# sensor_module_base_16F1454.net
KiCad netlist of a schematic drawn in EAGLE
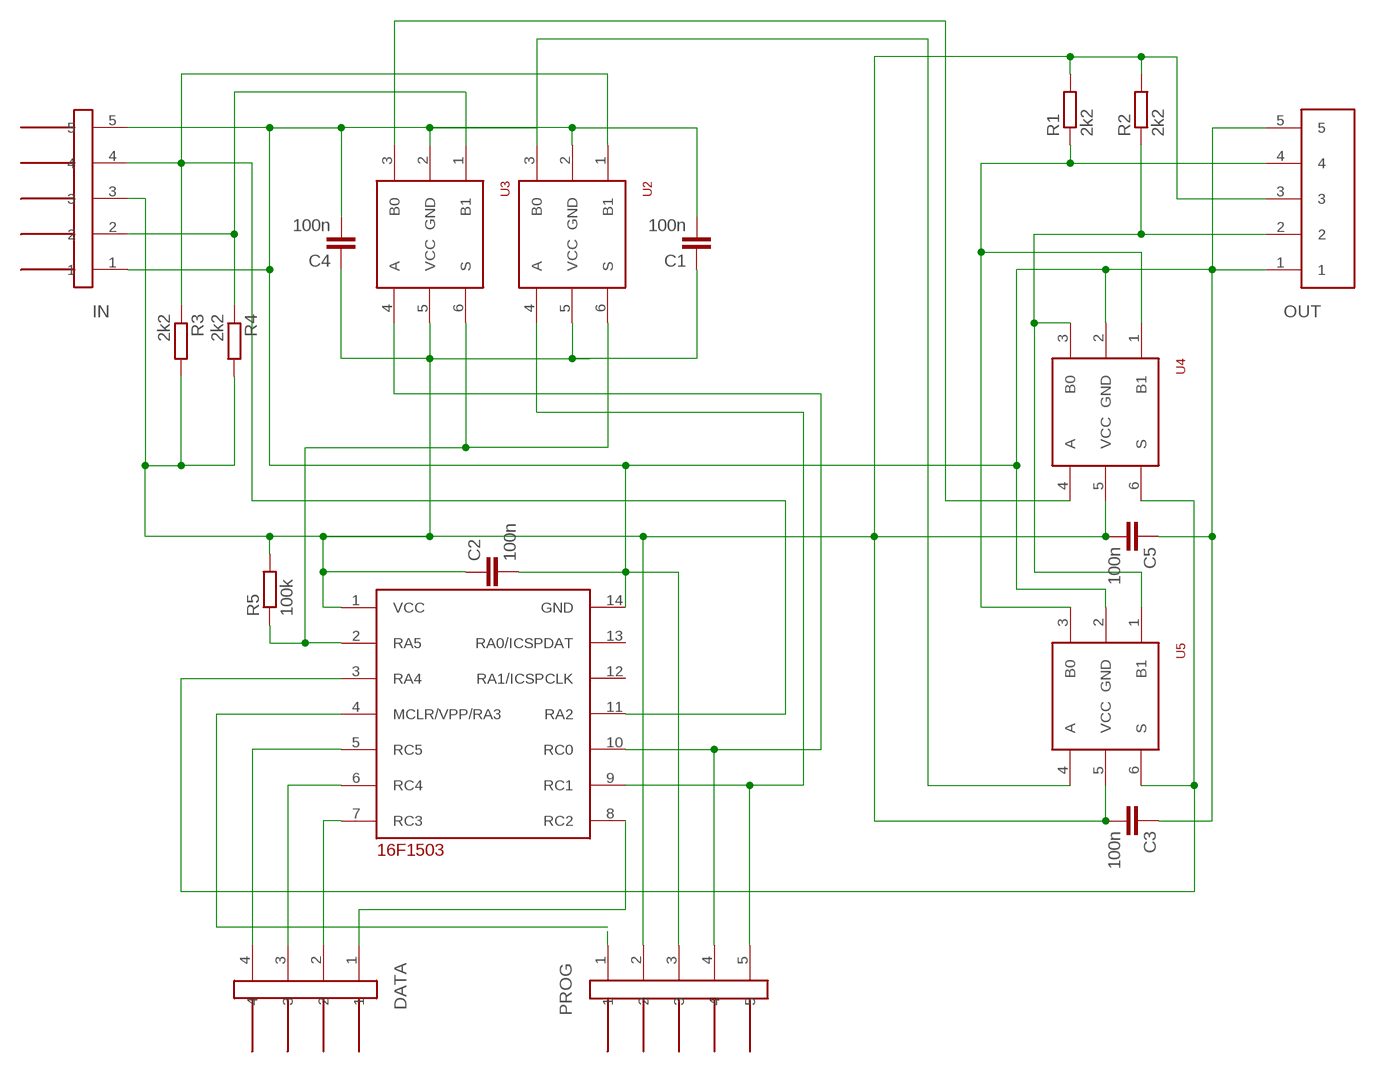
[diagram p0: schematic, sheet 1]

(export (version "E")
  (design (tool "Eeschema 10.0.6"))
  (components
    (comp (ref "C1")
      (value "100n")
      (footprint "eagle-import:C0603K")
      (libsource (lib "eagle-import") (part "C-EUC0603K"))
    )
    (comp (ref "C2")
      (value "100n")
      (footprint "eagle-import:C0603K")
      (libsource (lib "eagle-import") (part "C-EUC0603K"))
    )
    (comp (ref "C3")
      (value "100n")
      (footprint "eagle-import:C0603K")
      (libsource (lib "eagle-import") (part "C-EUC0603K"))
    )
    (comp (ref "C4")
      (value "100n")
      (footprint "eagle-import:C0603K")
      (libsource (lib "eagle-import") (part "C-EUC0603K"))
    )
    (comp (ref "C5")
      (value "100n")
      (footprint "eagle-import:C0603K")
      (libsource (lib "eagle-import") (part "C-EUC0603K"))
    )
    (comp (ref "DATA")
      (value "JUMPER4M")
      (footprint "eagle-import:JUMPER4M")
      (libsource (lib "eagle-import") (part "JUMPER4M"))
    )
    (comp (ref "IN")
      (value "JUMPER5M-90")
      (footprint "eagle-import:JUMPER5M-90")
      (libsource (lib "eagle-import") (part "JUMPER5M-90"))
    )
    (comp (ref "OUT")
      (value "JUMPER5F-90")
      (footprint "eagle-import:JUMPER5F-90")
      (libsource (lib "eagle-import") (part "JUMPER5F-90"))
    )
    (comp (ref "PROG")
      (value "JUMPER5M")
      (footprint "eagle-import:JUMPER5M")
      (libsource (lib "eagle-import") (part "JUMPER5M"))
    )
    (comp (ref "R1")
      (value "2k2")
      (footprint "eagle-import:R0603")
      (libsource (lib "eagle-import") (part "R-EU_R0603"))
    )
    (comp (ref "R2")
      (value "2k2")
      (footprint "eagle-import:R0603")
      (libsource (lib "eagle-import") (part "R-EU_R0603"))
    )
    (comp (ref "R3")
      (value "2k2")
      (footprint "eagle-import:R0603")
      (libsource (lib "eagle-import") (part "R-EU_R0603"))
    )
    (comp (ref "R4")
      (value "2k2")
      (footprint "eagle-import:R0603")
      (libsource (lib "eagle-import") (part "R-EU_R0603"))
    )
    (comp (ref "R5")
      (value "100k")
      (footprint "eagle-import:R0603")
      (libsource (lib "eagle-import") (part "R-EU_R0603"))
    )
    (comp (ref "U1")
      (value "16F1454")
      (footprint "eagle-import:TSSOP14")
      (libsource (lib "eagle-import") (part "16F103-TSSOP"))
    )
    (comp (ref "U2")
      (value "NC7SB3157P6X")
      (footprint "eagle-import:SC70-6L")
      (libsource (lib "eagle-import") (part "NC7SB3157P6X"))
    )
    (comp (ref "U3")
      (value "NC7SB3157P6X")
      (footprint "eagle-import:SC70-6L")
      (libsource (lib "eagle-import") (part "NC7SB3157P6X"))
    )
    (comp (ref "U4")
      (value "NC7SB3157P6X")
      (footprint "eagle-import:SC70-6L")
      (libsource (lib "eagle-import") (part "NC7SB3157P6X"))
    )
    (comp (ref "U5")
      (value "NC7SB3157P6X")
      (footprint "eagle-import:SC70-6L")
      (libsource (lib "eagle-import") (part "NC7SB3157P6X"))
    )
  )
  (nets
    (net (code "1") (name "Net-(U1-GND)") (class "Default")
      (node (ref "C1") (pin "2") (pinfunction "2_2") (pintype "passive"))
      (node (ref "C2") (pin "2") (pinfunction "2_2") (pintype "passive"))
      (node (ref "C3") (pin "1") (pinfunction "1_1") (pintype "passive"))
      (node (ref "C4") (pin "2") (pinfunction "2_2") (pintype "passive"))
      (node (ref "C5") (pin "1") (pinfunction "1_1") (pintype "passive"))
      (node (ref "IN") (pin "1") (pinfunction "1_1") (pintype "bidirectional"))
      (node (ref "IN") (pin "5") (pinfunction "5_5") (pintype "bidirectional"))
      (node (ref "OUT") (pin "1") (pinfunction "1_1") (pintype "bidirectional"))
      (node (ref "OUT") (pin "5") (pinfunction "5_5") (pintype "bidirectional"))
      (node (ref "PROG") (pin "3") (pinfunction "3_3") (pintype "bidirectional"))
      (node (ref "U1") (pin "14") (pinfunction "GND_14") (pintype "power_in"))
      (node (ref "U2") (pin "2") (pinfunction "GND_2") (pintype "power_in"))
      (node (ref "U3") (pin "2") (pinfunction "GND_2") (pintype "power_in"))
      (node (ref "U4") (pin "2") (pinfunction "GND_2") (pintype "power_in"))
      (node (ref "U5") (pin "2") (pinfunction "GND_2") (pintype "power_in"))
    )
    (net (code "2") (name "Net-(U1-MCLR{slash}VPP{slash}RA3)") (class "Default")
      (node (ref "PROG") (pin "1") (pinfunction "1_1") (pintype "bidirectional"))
      (node (ref "U1") (pin "4") (pinfunction "MCLR/VPP/RA3_4") (pintype "bidirectional"))
    )
    (net (code "3") (name "Net-(U1-RA2)") (class "Default")
      (node (ref "IN") (pin "4") (pinfunction "4_4") (pintype "bidirectional"))
      (node (ref "R3") (pin "1") (pinfunction "1_1") (pintype "passive"))
      (node (ref "U1") (pin "11") (pinfunction "RA2_11") (pintype "bidirectional"))
      (node (ref "U2") (pin "1") (pinfunction "B1_1") (pintype "bidirectional"))
    )
    (net (code "4") (name "Net-(U1-RA4)") (class "Default")
      (node (ref "U1") (pin "3") (pinfunction "RA4_3") (pintype "bidirectional"))
      (node (ref "U4") (pin "6") (pinfunction "S_6") (pintype "bidirectional"))
      (node (ref "U5") (pin "6") (pinfunction "S_6") (pintype "bidirectional"))
    )
    (net (code "5") (name "Net-(U1-RA5)") (class "Default")
      (node (ref "R5") (pin "1") (pinfunction "1_1") (pintype "passive"))
      (node (ref "U1") (pin "2") (pinfunction "RA5_2") (pintype "bidirectional"))
      (node (ref "U2") (pin "6") (pinfunction "S_6") (pintype "bidirectional"))
      (node (ref "U3") (pin "6") (pinfunction "S_6") (pintype "bidirectional"))
    )
    (net (code "6") (name "Net-(U1-RC0)") (class "Default")
      (node (ref "PROG") (pin "4") (pinfunction "4_4") (pintype "bidirectional"))
      (node (ref "U1") (pin "10") (pinfunction "RC0_10") (pintype "bidirectional"))
      (node (ref "U3") (pin "4") (pinfunction "A_4") (pintype "bidirectional"))
    )
    (net (code "7") (name "Net-(U1-RC1)") (class "Default")
      (node (ref "PROG") (pin "5") (pinfunction "5_5") (pintype "bidirectional"))
      (node (ref "U1") (pin "9") (pinfunction "RC1_9") (pintype "bidirectional"))
      (node (ref "U2") (pin "4") (pinfunction "A_4") (pintype "bidirectional"))
    )
    (net (code "8") (name "Net-(U1-RC2)") (class "Default")
      (node (ref "DATA") (pin "1") (pinfunction "1_1") (pintype "bidirectional"))
      (node (ref "U1") (pin "8") (pinfunction "RC2_8") (pintype "bidirectional"))
    )
    (net (code "9") (name "Net-(U1-RC3)") (class "Default")
      (node (ref "DATA") (pin "2") (pinfunction "2_2") (pintype "bidirectional"))
      (node (ref "U1") (pin "7") (pinfunction "RC3_7") (pintype "bidirectional"))
    )
    (net (code "10") (name "Net-(U1-RC4)") (class "Default")
      (node (ref "DATA") (pin "3") (pinfunction "3_3") (pintype "bidirectional"))
      (node (ref "U1") (pin "6") (pinfunction "RC4_6") (pintype "bidirectional"))
    )
    (net (code "11") (name "Net-(U1-RC5)") (class "Default")
      (node (ref "DATA") (pin "4") (pinfunction "4_4") (pintype "bidirectional"))
      (node (ref "U1") (pin "5") (pinfunction "RC5_5") (pintype "bidirectional"))
    )
    (net (code "12") (name "Net-(U1-VCC)") (class "Default")
      (node (ref "C1") (pin "1") (pinfunction "1_1") (pintype "passive"))
      (node (ref "C2") (pin "1") (pinfunction "1_1") (pintype "passive"))
      (node (ref "C3") (pin "2") (pinfunction "2_2") (pintype "passive"))
      (node (ref "C4") (pin "1") (pinfunction "1_1") (pintype "passive"))
      (node (ref "C5") (pin "2") (pinfunction "2_2") (pintype "passive"))
      (node (ref "IN") (pin "3") (pinfunction "3_3") (pintype "bidirectional"))
      (node (ref "OUT") (pin "3") (pinfunction "3_3") (pintype "bidirectional"))
      (node (ref "PROG") (pin "2") (pinfunction "2_2") (pintype "bidirectional"))
      (node (ref "R1") (pin "2") (pinfunction "2_2") (pintype "passive"))
      (node (ref "R2") (pin "2") (pinfunction "2_2") (pintype "passive"))
      (node (ref "R3") (pin "2") (pinfunction "2_2") (pintype "passive"))
      (node (ref "R4") (pin "2") (pinfunction "2_2") (pintype "passive"))
      (node (ref "R5") (pin "2") (pinfunction "2_2") (pintype "passive"))
      (node (ref "U1") (pin "1") (pinfunction "VCC_1") (pintype "power_in"))
      (node (ref "U2") (pin "5") (pinfunction "VCC_5") (pintype "power_in"))
      (node (ref "U3") (pin "5") (pinfunction "VCC_5") (pintype "power_in"))
      (node (ref "U4") (pin "5") (pinfunction "VCC_5") (pintype "power_in"))
      (node (ref "U5") (pin "5") (pinfunction "VCC_5") (pintype "power_in"))
    )
    (net (code "13") (name "Net-(U2-B0)") (class "Default")
      (node (ref "U2") (pin "3") (pinfunction "B0_3") (pintype "bidirectional"))
      (node (ref "U5") (pin "4") (pinfunction "A_4") (pintype "bidirectional"))
    )
    (net (code "14") (name "Net-(U3-B0)") (class "Default")
      (node (ref "U3") (pin "3") (pinfunction "B0_3") (pintype "bidirectional"))
      (node (ref "U4") (pin "4") (pinfunction "A_4") (pintype "bidirectional"))
    )
    (net (code "15") (name "Net-(U3-B1)") (class "Default")
      (node (ref "IN") (pin "2") (pinfunction "2_2") (pintype "bidirectional"))
      (node (ref "R4") (pin "1") (pinfunction "1_1") (pintype "passive"))
      (node (ref "U3") (pin "1") (pinfunction "B1_1") (pintype "bidirectional"))
    )
    (net (code "16") (name "Net-(U4-B0)") (class "Default")
      (node (ref "OUT") (pin "2") (pinfunction "2_2") (pintype "bidirectional"))
      (node (ref "R2") (pin "1") (pinfunction "1_1") (pintype "passive"))
      (node (ref "U4") (pin "3") (pinfunction "B0_3") (pintype "bidirectional"))
      (node (ref "U5") (pin "1") (pinfunction "B1_1") (pintype "bidirectional"))
    )
    (net (code "17") (name "Net-(U4-B1)") (class "Default")
      (node (ref "OUT") (pin "4") (pinfunction "4_4") (pintype "bidirectional"))
      (node (ref "R1") (pin "1") (pinfunction "1_1") (pintype "passive"))
      (node (ref "U4") (pin "1") (pinfunction "B1_1") (pintype "bidirectional"))
      (node (ref "U5") (pin "3") (pinfunction "B0_3") (pintype "bidirectional"))
    )
    (net (code "18") (name "unconnected-(U1-RA0{slash}ICSPDAT-Pad13)") (class "Default")
      (node (ref "U1") (pin "13") (pinfunction "RA0/ICSPDAT_13") (pintype "bidirectional"))
    )
    (net (code "19") (name "unconnected-(U1-RA1{slash}ICSPCLK-Pad12)") (class "Default")
      (node (ref "U1") (pin "12") (pinfunction "RA1/ICSPCLK_12") (pintype "bidirectional"))
    )
  )
)
